# 11_-_MOSFET.net
KiCad netlist of a schematic drawn in Altium Designer
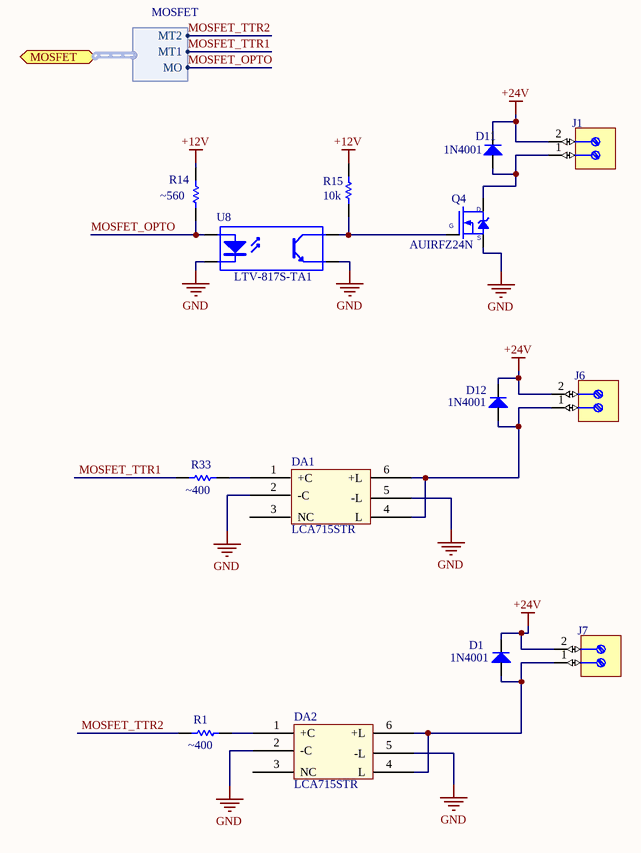
[diagram p0: [11] - MOSFET.SchDoc]

(export (version "E")
  (design (tool "Eeschema 10.0.6"))
  (components
    (comp (ref "D1")
      (value "1N4001")
      (description "1N4005")
      (libsource (lib "Blue Tractor-2021") (part "Diod"))
    )
    (comp (ref "D11")
      (value "1N4001")
      (description "1N4005")
      (libsource (lib "Blue Tractor-2021") (part "Diod"))
    )
    (comp (ref "D12")
      (value "1N4001")
      (description "1N4005")
      (libsource (lib "Blue Tractor-2021") (part "Diod"))
    )
    (comp (ref "DA1")
      (value "LCA715STR")
      (description "LCA715S-TTP")
      (libsource (lib "Blue Tractor-2021") (part "LCA715STR"))
    )
    (comp (ref "DA2")
      (value "LCA715STR")
      (description "LCA715S-TTP")
      (libsource (lib "Blue Tractor-2021") (part "LCA715STR"))
    )
    (comp (ref "J1")
      (value "~")
      (footprint "PHOENIX_1715721")
      (description "Terminal Block, 2 Positions, Screw Connection")
      (fields
        (field (name "PART NUMBER") "PHOENIX_1715721")
        (field (name "MANUFACTURER") "PHOENIX CONTACT")
        (field (name "AUTHOR") "CERN DEM JLC")
      )
      (libsource (lib "Connectors") (part "Terminal Block_2 Positions_Screw Connection"))
    )
    (comp (ref "J6")
      (value "~")
      (footprint "PHOENIX_1715721")
      (description "Terminal Block, 2 Positions, Screw Connection")
      (fields
        (field (name "PART NUMBER") "PHOENIX_1715721")
        (field (name "MANUFACTURER") "PHOENIX CONTACT")
        (field (name "AUTHOR") "CERN DEM JLC")
      )
      (libsource (lib "Connectors") (part "Terminal Block_2 Positions_Screw Connection"))
    )
    (comp (ref "J7")
      (value "~")
      (footprint "PHOENIX_1715721")
      (description "Terminal Block, 2 Positions, Screw Connection")
      (fields
        (field (name "PART NUMBER") "PHOENIX_1715721")
        (field (name "MANUFACTURER") "PHOENIX CONTACT")
        (field (name "AUTHOR") "CERN DEM JLC")
      )
      (libsource (lib "Connectors") (part "Terminal Block_2 Positions_Screw Connection"))
    )
    (comp (ref "Q4")
      (value "AUIRFZ24N")
      (description "N-Chanel MOSFET AUIRFZ24N")
      (libsource (lib "Blue Tractor-2021") (part "AUIRFZ24N"))
    )
    (comp (ref "R1")
      (value "~400")
      (footprint "Res-0603")
      (description "Chip Resistor")
      (fields
        (field (name "MANUFACTURER") "Stackpole Electronics Inc")
        (field (name "MANUFACTURER PART NUMBER") "RMCF0603JT3K60")
        (field (name "PUBLISHER") "Altium Limited")
      )
      (libsource (lib "Altium_Library") (part "Res1"))
    )
    (comp (ref "R14")
      (value "Res1")
      (footprint "Res-0603")
      (description "Chip Resistor")
      (fields
        (field (name "MANUFACTURER") "Panasonic")
        (field (name "MANUFACTURER PART NUMBER") "ERJ-3GEYJ222V")
        (field (name "RESISTANCE") "~560")
      )
      (libsource (lib "Altium_Library") (part "Res1"))
    )
    (comp (ref "R15")
      (value "Res1")
      (footprint "Res-0603")
      (description "Chip Resistor")
      (fields
        (field (name "MANUFACTURER") "Panasonic")
        (field (name "MANUFACTURER PART NUMBER") "ERJ-3GEYJ222V")
        (field (name "RESISTANCE") "10k")
      )
      (libsource (lib "Altium_Library") (part "Res1"))
    )
    (comp (ref "R33")
      (value "~400")
      (footprint "Res-0603")
      (description "Chip Resistor")
      (fields
        (field (name "MANUFACTURER") "Stackpole Electronics Inc")
        (field (name "MANUFACTURER PART NUMBER") "RMCF0603JT3K60")
        (field (name "PUBLISHER") "Altium Limited")
      )
      (libsource (lib "Altium_Library") (part "Res1"))
    )
    (comp (ref "U8")
      (value "Optoisolator1")
      (footprint "TLP184")
      (description "4-Pin Phototransistor Optocoupler")
      (fields
        (field (name "MANUFACTURER") "Toshiba")
        (field (name "MANUFACTURER PART NUMBER") "LTV-817S-TA1")
      )
      (libsource (lib "Miscellaneous Devices") (part "Optoisolator1"))
    )
  )
  (nets
    (net (code "2") (name "+12V") (class "Default")
      (node (ref "R14") (pin "2") (pinfunction "2_2") (pintype "passive"))
      (node (ref "R15") (pin "2") (pinfunction "2_2") (pintype "passive"))
    )
    (net (code "3") (name "+24V") (class "Default")
      (node (ref "D1") (pin "16") (pinfunction "16_16") (pintype "passive"))
      (node (ref "D11") (pin "16") (pinfunction "16_16") (pintype "passive"))
      (node (ref "D12") (pin "16") (pinfunction "16_16") (pintype "passive"))
      (node (ref "J1") (pin "2") (pinfunction "2_2") (pintype "bidirectional"))
      (node (ref "J6") (pin "2") (pinfunction "2_2") (pintype "bidirectional"))
      (node (ref "J7") (pin "2") (pinfunction "2_2") (pintype "bidirectional"))
    )
    (net (code "4") (name "/MOSFET_OPTO") (class "Default")
      (node (ref "R14") (pin "1") (pinfunction "1_1") (pintype "passive"))
      (node (ref "U8") (pin "1") (pinfunction "A_1") (pintype "passive"))
    )
    (net (code "5") (name "/MOSFET_TTR1") (class "Default")
      (node (ref "R33") (pin "2") (pinfunction "2_2") (pintype "passive"))
    )
    (net (code "6") (name "/MOSFET_TTR2") (class "Default")
      (node (ref "R1") (pin "2") (pinfunction "2_2") (pintype "passive"))
    )
    (net (code "8") (name "GND") (class "Default")
      (node (ref "DA1") (pin "2") (pinfunction "-C_2") (pintype "power_in"))
      (node (ref "DA1") (pin "5") (pinfunction "-L_5") (pintype "power_in"))
      (node (ref "DA2") (pin "2") (pinfunction "-C_2") (pintype "power_in"))
      (node (ref "DA2") (pin "5") (pinfunction "-L_5") (pintype "power_in"))
      (node (ref "Q4") (pin "17") (pinfunction "17_17") (pintype "passive"))
      (node (ref "U8") (pin "2") (pinfunction "K_2") (pintype "passive"))
      (node (ref "U8") (pin "3") (pinfunction "E_3") (pintype "passive"))
    )
    (net (code "9") (name "Net-(D11-Pad16)") (class "Default")
      (node (ref "D11") (pin "16") (pinfunction "16_16") (pintype "passive"))
      (node (ref "J1") (pin "1") (pinfunction "1_1") (pintype "bidirectional"))
      (node (ref "Q4") (pin "16") (pinfunction "16_16") (pintype "passive"))
    )
    (net (code "10") (name "Net-(DA1-+C)") (class "Default")
      (node (ref "DA1") (pin "1") (pinfunction "+C_1") (pintype "power_in"))
      (node (ref "R33") (pin "1") (pinfunction "1_1") (pintype "passive"))
    )
    (net (code "11") (name "Net-(DA1-+L)") (class "Default")
      (node (ref "D12") (pin "16") (pinfunction "16_16") (pintype "passive"))
      (node (ref "DA1") (pin "4") (pinfunction "L_4") (pintype "power_in"))
      (node (ref "DA1") (pin "6") (pinfunction "+L_6") (pintype "power_in"))
      (node (ref "J6") (pin "1") (pinfunction "1_1") (pintype "bidirectional"))
    )
    (net (code "12") (name "Net-(DA2-+C)") (class "Default")
      (node (ref "DA2") (pin "1") (pinfunction "+C_1") (pintype "power_in"))
      (node (ref "R1") (pin "1") (pinfunction "1_1") (pintype "passive"))
    )
    (net (code "13") (name "Net-(DA2-+L)") (class "Default")
      (node (ref "D1") (pin "16") (pinfunction "16_16") (pintype "passive"))
      (node (ref "DA2") (pin "4") (pinfunction "L_4") (pintype "power_in"))
      (node (ref "DA2") (pin "6") (pinfunction "+L_6") (pintype "power_in"))
      (node (ref "J7") (pin "1") (pinfunction "1_1") (pintype "bidirectional"))
    )
    (net (code "14") (name "Net-(Q4-PG)") (class "Default")
      (node (ref "Q4") (pin "15") (pinfunction "PG_15") (pintype "passive"))
      (node (ref "R15") (pin "1") (pinfunction "1_1") (pintype "passive"))
      (node (ref "U8") (pin "4") (pinfunction "C_4") (pintype "passive"))
    )
    (net (code "15") (name "unconnected-(DA1-NC-Pad3)") (class "Default")
      (node (ref "DA1") (pin "3") (pinfunction "NC_3") (pintype "power_in"))
    )
    (net (code "16") (name "unconnected-(DA2-NC-Pad3)") (class "Default")
      (node (ref "DA2") (pin "3") (pinfunction "NC_3") (pintype "power_in"))
    )
  )
)
